# arduino-breadboard.net
KiCad netlist of a schematic drawn in EAGLE
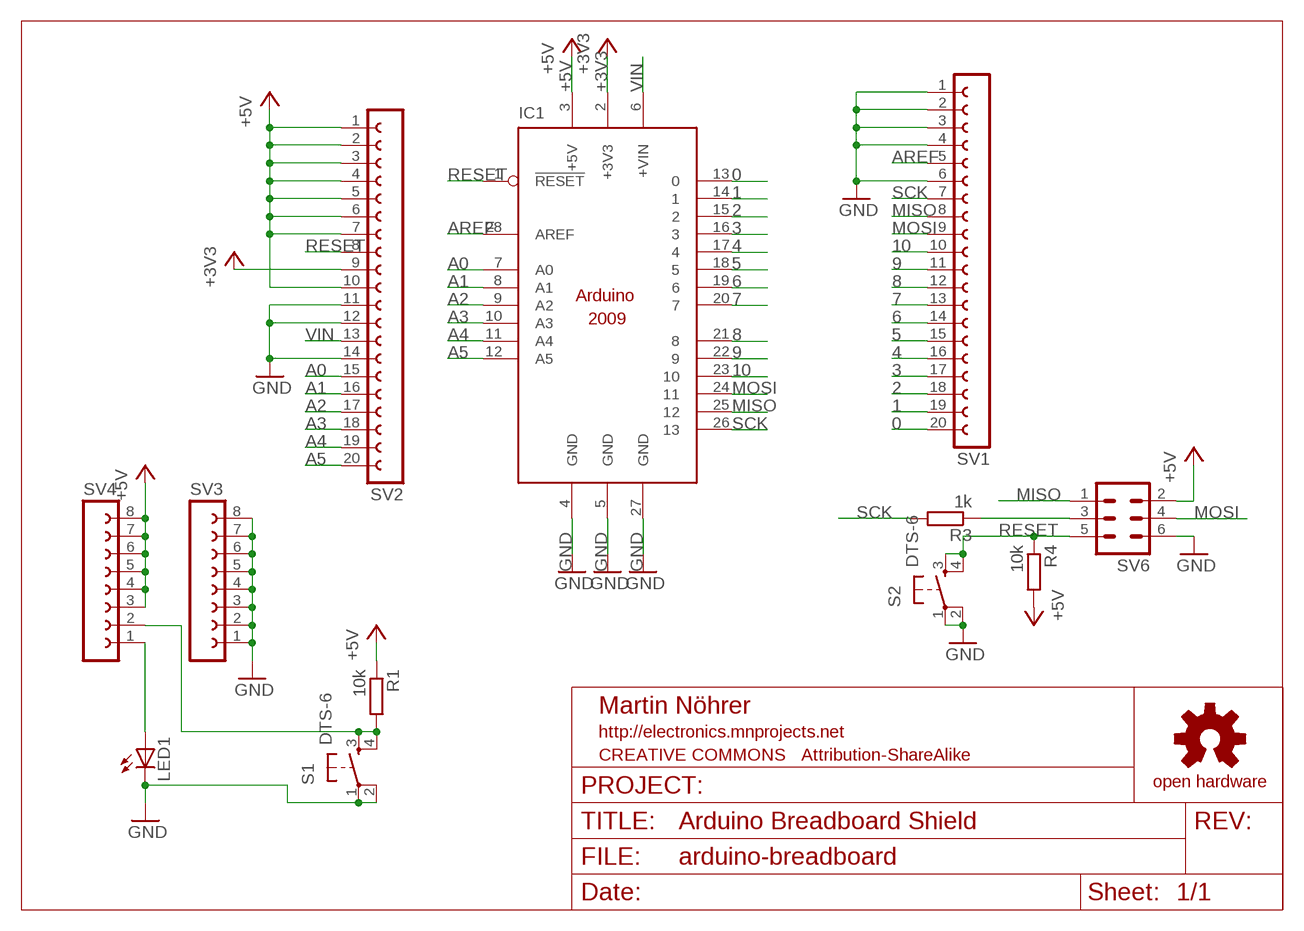
[diagram p0: schematic, sheet 1]

(export (version "E")
  (design (tool "Eeschema 10.0.6"))
  (components
    (comp (ref "IC1")
      (value "ARDUINO2009_12")
      (footprint "eagle-import:ARDUINO2009_2")
      (libsource (lib "eagle-import") (part "ARDUINO2009_12"))
    )
    (comp (ref "LED1")
      (value "LED5MM")
      (footprint "eagle-import:LED5MM")
      (libsource (lib "eagle-import") (part "LED5MM"))
    )
    (comp (ref "R1")
      (value "10k")
      (footprint "eagle-import:0207_10")
      (libsource (lib "eagle-import") (part "R-EU_0207/10"))
    )
    (comp (ref "R3")
      (value "1k")
      (footprint "eagle-import:0207_10")
      (libsource (lib "eagle-import") (part "R-EU_0207/10"))
    )
    (comp (ref "R4")
      (value "10k")
      (footprint "eagle-import:0207_10")
      (libsource (lib "eagle-import") (part "R-EU_0207/10"))
    )
    (comp (ref "S1")
      (value "DTS-6")
      (footprint "eagle-import:DTS-6")
      (libsource (lib "eagle-import") (part "DTS-6"))
    )
    (comp (ref "S2")
      (value "DTS-6")
      (footprint "eagle-import:DTS-6")
      (libsource (lib "eagle-import") (part "DTS-6"))
    )
    (comp (ref "SV1")
      (value "FE20-1")
      (footprint "eagle-import:FE20")
      (libsource (lib "eagle-import") (part "FE20-1"))
    )
    (comp (ref "SV2")
      (value "FE20-1")
      (footprint "eagle-import:FE20")
      (libsource (lib "eagle-import") (part "FE20-1"))
    )
    (comp (ref "SV3")
      (value "FE08-1")
      (footprint "eagle-import:FE08")
      (libsource (lib "eagle-import") (part "FE08-1"))
    )
    (comp (ref "SV4")
      (value "FE08-1")
      (footprint "eagle-import:FE08")
      (libsource (lib "eagle-import") (part "FE08-1"))
    )
    (comp (ref "SV6")
      (value "MA03-2")
      (footprint "eagle-import:MA03-2")
      (libsource (lib "eagle-import") (part "MA03-2"))
    )
  )
  (nets
    (net (code "1") (name "+3V3") (class "Default")
      (node (ref "IC1") (pin "2") (pinfunction "+3V3_2") (pintype "power_in"))
      (node (ref "SV2") (pin "9") (pinfunction "9_9") (pintype "passive"))
    )
    (net (code "2") (name "+5V") (class "Default")
      (node (ref "IC1") (pin "3") (pinfunction "+5V_3") (pintype "power_in"))
      (node (ref "R1") (pin "1") (pinfunction "1_1") (pintype "passive"))
      (node (ref "R4") (pin "2") (pinfunction "2_2") (pintype "passive"))
      (node (ref "SV2") (pin "1") (pinfunction "1_1") (pintype "passive"))
      (node (ref "SV2") (pin "10") (pinfunction "10_10") (pintype "passive"))
      (node (ref "SV2") (pin "2") (pinfunction "2_2") (pintype "passive"))
      (node (ref "SV2") (pin "3") (pinfunction "3_3") (pintype "passive"))
      (node (ref "SV2") (pin "4") (pinfunction "4_4") (pintype "passive"))
      (node (ref "SV2") (pin "5") (pinfunction "5_5") (pintype "passive"))
      (node (ref "SV2") (pin "6") (pinfunction "6_6") (pintype "passive"))
      (node (ref "SV2") (pin "7") (pinfunction "7_7") (pintype "passive"))
      (node (ref "SV4") (pin "3") (pinfunction "3_3") (pintype "passive"))
      (node (ref "SV4") (pin "4") (pinfunction "4_4") (pintype "passive"))
      (node (ref "SV4") (pin "5") (pinfunction "5_5") (pintype "passive"))
      (node (ref "SV4") (pin "6") (pinfunction "6_6") (pintype "passive"))
      (node (ref "SV4") (pin "7") (pinfunction "7_7") (pintype "passive"))
      (node (ref "SV4") (pin "8") (pinfunction "8_8") (pintype "passive"))
      (node (ref "SV6") (pin "2") (pinfunction "2_2") (pintype "passive"))
    )
    (net (code "3") (name "/0") (class "Default")
      (node (ref "IC1") (pin "13") (pinfunction "0_13") (pintype "bidirectional"))
      (node (ref "SV1") (pin "20") (pinfunction "20_20") (pintype "passive"))
    )
    (net (code "4") (name "/1") (class "Default")
      (node (ref "IC1") (pin "14") (pinfunction "1_14") (pintype "bidirectional"))
      (node (ref "SV1") (pin "19") (pinfunction "19_19") (pintype "passive"))
    )
    (net (code "5") (name "/2") (class "Default")
      (node (ref "IC1") (pin "15") (pinfunction "2_15") (pintype "bidirectional"))
      (node (ref "SV1") (pin "18") (pinfunction "18_18") (pintype "passive"))
    )
    (net (code "6") (name "/3") (class "Default")
      (node (ref "IC1") (pin "16") (pinfunction "3_16") (pintype "bidirectional"))
      (node (ref "SV1") (pin "17") (pinfunction "17_17") (pintype "passive"))
    )
    (net (code "7") (name "/4") (class "Default")
      (node (ref "IC1") (pin "17") (pinfunction "4_17") (pintype "bidirectional"))
      (node (ref "SV1") (pin "16") (pinfunction "16_16") (pintype "passive"))
    )
    (net (code "8") (name "/5") (class "Default")
      (node (ref "IC1") (pin "18") (pinfunction "5_18") (pintype "bidirectional"))
      (node (ref "SV1") (pin "15") (pinfunction "15_15") (pintype "passive"))
    )
    (net (code "9") (name "/6") (class "Default")
      (node (ref "IC1") (pin "19") (pinfunction "6_19") (pintype "bidirectional"))
      (node (ref "SV1") (pin "14") (pinfunction "14_14") (pintype "passive"))
    )
    (net (code "10") (name "/7") (class "Default")
      (node (ref "IC1") (pin "20") (pinfunction "7_20") (pintype "bidirectional"))
      (node (ref "SV1") (pin "13") (pinfunction "13_13") (pintype "passive"))
    )
    (net (code "11") (name "/8") (class "Default")
      (node (ref "IC1") (pin "21") (pinfunction "8_21") (pintype "bidirectional"))
      (node (ref "SV1") (pin "12") (pinfunction "12_12") (pintype "passive"))
    )
    (net (code "12") (name "/9") (class "Default")
      (node (ref "IC1") (pin "22") (pinfunction "9_22") (pintype "bidirectional"))
      (node (ref "SV1") (pin "11") (pinfunction "11_11") (pintype "passive"))
    )
    (net (code "13") (name "/10") (class "Default")
      (node (ref "IC1") (pin "23") (pinfunction "10_23") (pintype "bidirectional"))
      (node (ref "SV1") (pin "10") (pinfunction "10_10") (pintype "passive"))
    )
    (net (code "14") (name "/A0") (class "Default")
      (node (ref "IC1") (pin "7") (pinfunction "A0_7") (pintype "bidirectional"))
      (node (ref "SV2") (pin "15") (pinfunction "15_15") (pintype "passive"))
    )
    (net (code "15") (name "/A1") (class "Default")
      (node (ref "IC1") (pin "8") (pinfunction "A1_8") (pintype "bidirectional"))
      (node (ref "SV2") (pin "16") (pinfunction "16_16") (pintype "passive"))
    )
    (net (code "16") (name "/A2") (class "Default")
      (node (ref "IC1") (pin "9") (pinfunction "A2_9") (pintype "bidirectional"))
      (node (ref "SV2") (pin "17") (pinfunction "17_17") (pintype "passive"))
    )
    (net (code "17") (name "/A3") (class "Default")
      (node (ref "IC1") (pin "10") (pinfunction "A3_10") (pintype "bidirectional"))
      (node (ref "SV2") (pin "18") (pinfunction "18_18") (pintype "passive"))
    )
    (net (code "18") (name "/A4") (class "Default")
      (node (ref "IC1") (pin "11") (pinfunction "A4_11") (pintype "bidirectional"))
      (node (ref "SV2") (pin "19") (pinfunction "19_19") (pintype "passive"))
    )
    (net (code "19") (name "/A5") (class "Default")
      (node (ref "IC1") (pin "12") (pinfunction "A5_12") (pintype "bidirectional"))
      (node (ref "SV2") (pin "20") (pinfunction "20_20") (pintype "passive"))
    )
    (net (code "20") (name "/AREF") (class "Default")
      (node (ref "IC1") (pin "28") (pinfunction "AREF_28") (pintype "bidirectional"))
      (node (ref "SV1") (pin "5") (pinfunction "5_5") (pintype "passive"))
    )
    (net (code "21") (name "/MISO") (class "Default")
      (node (ref "IC1") (pin "25") (pinfunction "12_25") (pintype "bidirectional"))
      (node (ref "SV1") (pin "8") (pinfunction "8_8") (pintype "passive"))
      (node (ref "SV6") (pin "1") (pinfunction "1_1") (pintype "passive"))
    )
    (net (code "22") (name "/MOSI") (class "Default")
      (node (ref "IC1") (pin "24") (pinfunction "11_24") (pintype "bidirectional"))
      (node (ref "SV1") (pin "9") (pinfunction "9_9") (pintype "passive"))
      (node (ref "SV6") (pin "4") (pinfunction "4_4") (pintype "passive"))
    )
    (net (code "23") (name "/RESET") (class "Default")
      (node (ref "IC1") (pin "1") (pinfunction "~{RESET}_1") (pintype "bidirectional"))
      (node (ref "R4") (pin "1") (pinfunction "1_1") (pintype "passive"))
      (node (ref "S2") (pin "3") (pinfunction "3_3") (pintype "passive"))
      (node (ref "S2") (pin "4") (pinfunction "4_4") (pintype "passive"))
      (node (ref "SV2") (pin "8") (pinfunction "8_8") (pintype "passive"))
      (node (ref "SV6") (pin "5") (pinfunction "5_5") (pintype "passive"))
    )
    (net (code "24") (name "/SCK") (class "Default")
      (node (ref "IC1") (pin "26") (pinfunction "13_26") (pintype "bidirectional"))
      (node (ref "R3") (pin "2") (pinfunction "2_2") (pintype "passive"))
      (node (ref "SV1") (pin "7") (pinfunction "7_7") (pintype "passive"))
    )
    (net (code "25") (name "/VIN") (class "Default")
      (node (ref "IC1") (pin "6") (pinfunction "+VIN_6") (pintype "bidirectional"))
      (node (ref "SV2") (pin "13") (pinfunction "13_13") (pintype "passive"))
    )
    (net (code "26") (name "GND") (class "Default")
      (node (ref "IC1") (pin "27") (pinfunction "GND_27") (pintype "power_in"))
      (node (ref "IC1") (pin "4") (pinfunction "GND_4") (pintype "power_in"))
      (node (ref "IC1") (pin "5") (pinfunction "GND_5") (pintype "power_in"))
      (node (ref "LED1") (pin "K") (pinfunction "C_K") (pintype "passive"))
      (node (ref "S1") (pin "1") (pinfunction "1_1") (pintype "passive"))
      (node (ref "S1") (pin "2") (pinfunction "2_2") (pintype "passive"))
      (node (ref "S2") (pin "1") (pinfunction "1_1") (pintype "passive"))
      (node (ref "S2") (pin "2") (pinfunction "2_2") (pintype "passive"))
      (node (ref "SV1") (pin "1") (pinfunction "1_1") (pintype "passive"))
      (node (ref "SV1") (pin "2") (pinfunction "2_2") (pintype "passive"))
      (node (ref "SV1") (pin "3") (pinfunction "3_3") (pintype "passive"))
      (node (ref "SV1") (pin "4") (pinfunction "4_4") (pintype "passive"))
      (node (ref "SV1") (pin "6") (pinfunction "6_6") (pintype "passive"))
      (node (ref "SV2") (pin "11") (pinfunction "11_11") (pintype "passive"))
      (node (ref "SV2") (pin "12") (pinfunction "12_12") (pintype "passive"))
      (node (ref "SV2") (pin "14") (pinfunction "14_14") (pintype "passive"))
      (node (ref "SV3") (pin "1") (pinfunction "1_1") (pintype "passive"))
      (node (ref "SV3") (pin "2") (pinfunction "2_2") (pintype "passive"))
      (node (ref "SV3") (pin "3") (pinfunction "3_3") (pintype "passive"))
      (node (ref "SV3") (pin "4") (pinfunction "4_4") (pintype "passive"))
      (node (ref "SV3") (pin "5") (pinfunction "5_5") (pintype "passive"))
      (node (ref "SV3") (pin "6") (pinfunction "6_6") (pintype "passive"))
      (node (ref "SV3") (pin "7") (pinfunction "7_7") (pintype "passive"))
      (node (ref "SV3") (pin "8") (pinfunction "8_8") (pintype "passive"))
      (node (ref "SV6") (pin "6") (pinfunction "6_6") (pintype "passive"))
    )
    (net (code "27") (name "Net-(LED1-PadA)") (class "Default")
      (node (ref "LED1") (pin "A") (pinfunction "A_A") (pintype "passive"))
      (node (ref "SV4") (pin "1") (pinfunction "1_1") (pintype "passive"))
    )
    (net (code "28") (name "Net-(R1-Pad2)") (class "Default")
      (node (ref "R1") (pin "2") (pinfunction "2_2") (pintype "passive"))
      (node (ref "S1") (pin "3") (pinfunction "3_3") (pintype "passive"))
      (node (ref "S1") (pin "4") (pinfunction "4_4") (pintype "passive"))
      (node (ref "SV4") (pin "2") (pinfunction "2_2") (pintype "passive"))
    )
    (net (code "29") (name "Net-(R3-Pad1)") (class "Default")
      (node (ref "R3") (pin "1") (pinfunction "1_1") (pintype "passive"))
      (node (ref "SV6") (pin "3") (pinfunction "3_3") (pintype "passive"))
    )
  )
)
